# Power_Switching_Circuit_rev2.net
KiCad netlist of a schematic drawn in EAGLE
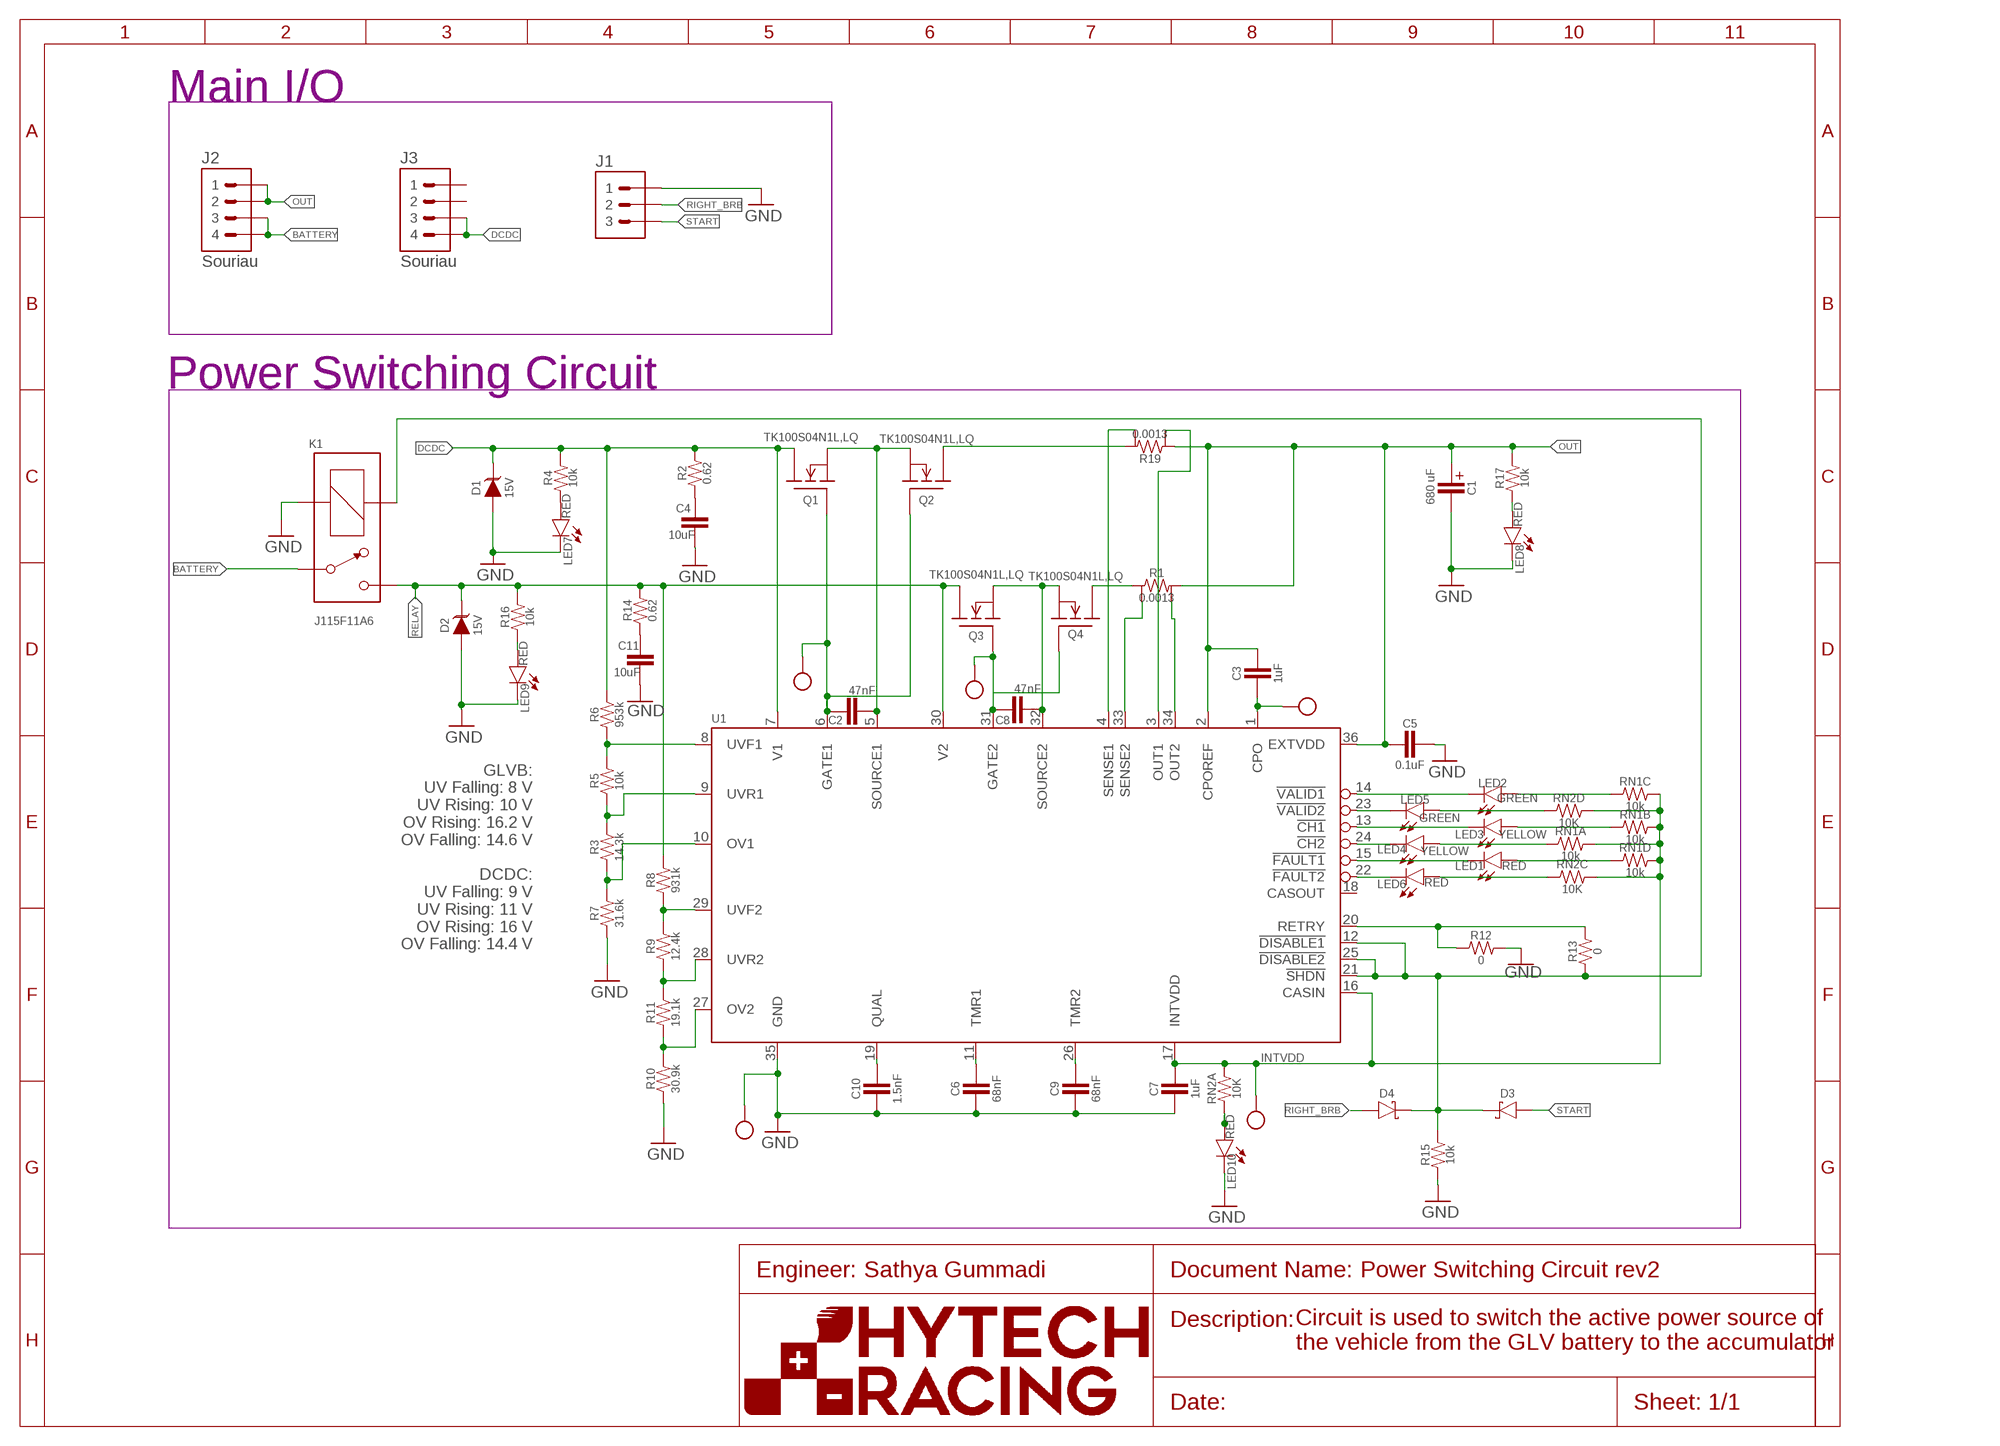
[diagram p0: schematic, sheet 1]

(export (version "E")
  (design (tool "Eeschema 10.0.6"))
  (components
    (comp (ref "C1")
      (value "CAPACITOR_POLARIZED")
      (footprint "eagle-import:EEE-FK1H681AM")
      (libsource (lib "eagle-import") (part "CAPACITOR_POLARIZED"))
    )
    (comp (ref "C2")
      (value "47nF")
      (footprint "eagle-import:0603-CAP@1")
      (libsource (lib "eagle-import") (part "CAP0603-CAP"))
    )
    (comp (ref "C3")
      (value "1uF")
      (footprint "eagle-import:0805")
      (libsource (lib "eagle-import") (part "CAP0805"))
    )
    (comp (ref "C4")
      (value "10uF")
      (footprint "eagle-import:1206-CAP")
      (libsource (lib "eagle-import") (part "CAPACITOR_VALUE1206"))
    )
    (comp (ref "C5")
      (value "0.1uF")
      (footprint "eagle-import:0603-CAP@1")
      (libsource (lib "eagle-import") (part "CAP0603-CAP"))
    )
    (comp (ref "C6")
      (value "68nF")
      (footprint "eagle-import:0603-CAP@1")
      (libsource (lib "eagle-import") (part "CAP0603-CAP"))
    )
    (comp (ref "C7")
      (value "1uF")
      (footprint "eagle-import:0805")
      (libsource (lib "eagle-import") (part "CAP0805"))
    )
    (comp (ref "C8")
      (value "47nF")
      (footprint "eagle-import:0603-CAP@1")
      (libsource (lib "eagle-import") (part "CAP0603-CAP"))
    )
    (comp (ref "C9")
      (value "68nF")
      (footprint "eagle-import:0603-CAP@1")
      (libsource (lib "eagle-import") (part "CAP0603-CAP"))
    )
    (comp (ref "C10")
      (value "1.5nF")
      (footprint "eagle-import:0603-CAP@1")
      (libsource (lib "eagle-import") (part "CAP0603-CAP"))
    )
    (comp (ref "C11")
      (value "10uF")
      (footprint "eagle-import:1206-CAP")
      (libsource (lib "eagle-import") (part "CAPACITOR_VALUE1206"))
    )
    (comp (ref "D1")
      (value "TVS_15V")
      (footprint "eagle-import:SOT-23")
      (fields
        (field (name "MANUFACTURER") "Vishay General Semiconductor - Diodes Division")
        (field (name "MPN") "GSOT15-E3-08")
        (field (name "VOLTAGE") "15V")
      )
      (libsource (lib "eagle-import") (part "TVS_15V"))
    )
    (comp (ref "D2")
      (value "TVS_15V")
      (footprint "eagle-import:SOT-23")
      (fields
        (field (name "MANUFACTURER") "Vishay General Semiconductor - Diodes Division")
        (field (name "MPN") "GSOT15-E3-08")
        (field (name "VOLTAGE") "15V")
      )
      (libsource (lib "eagle-import") (part "TVS_15V"))
    )
    (comp (ref "D3")
      (value "SCHOTTKY")
      (footprint "eagle-import:CLP1608-2L")
      (fields
        (field (name "MANUFACTURER") "Vishay General Semiconductor - Diodes Division")
        (field (name "MPN") "VSKY20401608-G4-08")
      )
      (libsource (lib "eagle-import") (part "SCHOTTKY"))
    )
    (comp (ref "D4")
      (value "SCHOTTKY")
      (footprint "eagle-import:CLP1608-2L")
      (fields
        (field (name "MANUFACTURER") "Vishay General Semiconductor - Diodes Division")
        (field (name "MPN") "VSKY20401608-G4-08")
      )
      (libsource (lib "eagle-import") (part "SCHOTTKY"))
    )
    (comp (ref "J1")
      (value "CONNECTOR-3_")
      (footprint "eagle-import:SOURIAU_04-35")
      (libsource (lib "eagle-import") (part "CONNECTOR-3_?"))
    )
    (comp (ref "J2")
      (value "CONNECTOR-4_SOURIAU_")
      (footprint "eagle-import:SOURIAU_12-04")
      (fields
        (field (name "MODEL") "Souriau")
        (field (name "MANUFACTURER") "Souriau")
        (field (name "MPN") "8STA21204PN ")
      )
      (libsource (lib "eagle-import") (part "CONNECTOR-4_?_SOURIAU"))
    )
    (comp (ref "J3")
      (value "CONNECTOR-4_SOURIAU_")
      (footprint "eagle-import:SOURIAU_12-04")
      (fields
        (field (name "MODEL") "Souriau")
        (field (name "MANUFACTURER") "Souriau")
        (field (name "MPN") "8STA21204PN ")
      )
      (libsource (lib "eagle-import") (part "CONNECTOR-4_?_SOURIAU"))
    )
    (comp (ref "K1")
      (value "J115F11A6")
      (footprint "eagle-import:J115F11A_6_")
      (libsource (lib "eagle-import") (part "J115F11A6"))
    )
    (comp (ref "LED1")
      (value "RED")
      (footprint "eagle-import:LED-603")
      (libsource (lib "eagle-import") (part "LED-0603"))
    )
    (comp (ref "LED2")
      (value "GREEN")
      (footprint "eagle-import:LED-603")
      (libsource (lib "eagle-import") (part "LED-0603"))
    )
    (comp (ref "LED3")
      (value "YELLOW")
      (footprint "eagle-import:LED-603")
      (libsource (lib "eagle-import") (part "LED-0603"))
    )
    (comp (ref "LED4")
      (value "YELLOW")
      (footprint "eagle-import:LED-603")
      (libsource (lib "eagle-import") (part "LED-0603"))
    )
    (comp (ref "LED5")
      (value "GREEN")
      (footprint "eagle-import:LED-603")
      (libsource (lib "eagle-import") (part "LED-0603"))
    )
    (comp (ref "LED6")
      (value "RED")
      (footprint "eagle-import:LED-603")
      (libsource (lib "eagle-import") (part "LED-0603"))
    )
    (comp (ref "LED7")
      (value "RED")
      (footprint "eagle-import:LED-603")
      (libsource (lib "eagle-import") (part "LED-0603"))
    )
    (comp (ref "LED8")
      (value "RED")
      (footprint "eagle-import:LED-603")
      (libsource (lib "eagle-import") (part "LED-0603"))
    )
    (comp (ref "LED9")
      (value "RED")
      (footprint "eagle-import:LED-603")
      (libsource (lib "eagle-import") (part "LED-0603"))
    )
    (comp (ref "LED10")
      (value "RED")
      (footprint "eagle-import:LED-603")
      (libsource (lib "eagle-import") (part "LED-0603"))
    )
    (comp (ref "Q1")
      (value "TK100S04N1L")
      (footprint "eagle-import:TO-252-3")
      (fields (field (name "MPN") "TK100S04N1L,LQ"))
      (libsource (lib "eagle-import") (part "TK100S04N1L"))
    )
    (comp (ref "Q2")
      (value "TK100S04N1L")
      (footprint "eagle-import:TO-252-3")
      (fields (field (name "MPN") "TK100S04N1L,LQ"))
      (libsource (lib "eagle-import") (part "TK100S04N1L"))
    )
    (comp (ref "Q3")
      (value "TK100S04N1L")
      (footprint "eagle-import:TO-252-3")
      (fields (field (name "MPN") "TK100S04N1L,LQ"))
      (libsource (lib "eagle-import") (part "TK100S04N1L"))
    )
    (comp (ref "Q4")
      (value "TK100S04N1L")
      (footprint "eagle-import:TO-252-3")
      (fields (field (name "MPN") "TK100S04N1L,LQ"))
      (libsource (lib "eagle-import") (part "TK100S04N1L"))
    )
    (comp (ref "R1")
      (value "RESISTOR_SENSE")
      (footprint "eagle-import:WSL2726")
      (fields (field (name "RESISTANCE") "0.0013") (field (name "MPN") "WSL2726"))
      (libsource (lib "eagle-import") (part "RESISTOR_SENSE"))
    )
    (comp (ref "R2")
      (value "0.62")
      (footprint "eagle-import:0805")
      (libsource (lib "eagle-import") (part "RESISTOR0805"))
    )
    (comp (ref "R3")
      (value "14.3k")
      (footprint "eagle-import:0603-RES")
      (libsource (lib "eagle-import") (part "RESISTOR0603"))
    )
    (comp (ref "R4")
      (value "10k")
      (footprint "eagle-import:0603-RES")
      (libsource (lib "eagle-import") (part "RESISTOR0603"))
    )
    (comp (ref "R5")
      (value "10k")
      (footprint "eagle-import:0603-RES")
      (libsource (lib "eagle-import") (part "RESISTOR0603"))
    )
    (comp (ref "R6")
      (value "953k")
      (footprint "eagle-import:0603-RES")
      (libsource (lib "eagle-import") (part "RESISTOR0603"))
    )
    (comp (ref "R7")
      (value "31.6k")
      (footprint "eagle-import:0603-RES")
      (libsource (lib "eagle-import") (part "RESISTOR0603"))
    )
    (comp (ref "R8")
      (value "931k")
      (footprint "eagle-import:0603-RES")
      (libsource (lib "eagle-import") (part "RESISTOR0603"))
    )
    (comp (ref "R9")
      (value "12.4k")
      (footprint "eagle-import:0603-RES")
      (libsource (lib "eagle-import") (part "RESISTOR0603"))
    )
    (comp (ref "R10")
      (value "30.9k")
      (footprint "eagle-import:0603-RES")
      (libsource (lib "eagle-import") (part "RESISTOR0603"))
    )
    (comp (ref "R11")
      (value "19.1k")
      (footprint "eagle-import:0603-RES")
      (libsource (lib "eagle-import") (part "RESISTOR0603"))
    )
    (comp (ref "R12")
      (value "0")
      (footprint "eagle-import:0603-RES")
      (libsource (lib "eagle-import") (part "RESISTOR0603"))
    )
    (comp (ref "R13")
      (value "0")
      (footprint "eagle-import:0603-RES")
      (libsource (lib "eagle-import") (part "RESISTOR0603"))
    )
    (comp (ref "R14")
      (value "0.62")
      (footprint "eagle-import:0805")
      (libsource (lib "eagle-import") (part "RESISTOR0805"))
    )
    (comp (ref "R15")
      (value "10k")
      (footprint "eagle-import:0603-RES")
      (libsource (lib "eagle-import") (part "RESISTOR0603"))
    )
    (comp (ref "R16")
      (value "10k")
      (footprint "eagle-import:0603-RES")
      (libsource (lib "eagle-import") (part "RESISTOR0603"))
    )
    (comp (ref "R17")
      (value "10k")
      (footprint "eagle-import:0603-RES")
      (libsource (lib "eagle-import") (part "RESISTOR0603"))
    )
    (comp (ref "R19")
      (value "RESISTOR_SENSE")
      (footprint "eagle-import:WSL2726")
      (fields (field (name "RESISTANCE") "0.0013") (field (name "MPN") "WSL2726"))
      (libsource (lib "eagle-import") (part "RESISTOR_SENSE"))
    )
    (comp (ref "RN1")
      (value "RESISTOR_NETWORK_4_10K")
      (footprint "eagle-import:YC_TC164")
      (fields (field (name "RESISTANCE") "10k"))
      (libsource (lib "eagle-import") (part "HyTechDevices - Copy_RESISTOR_NETWORK_4_10K"))
    )
    (comp (ref "RN2")
      (value "RESISTOR_NETWORK_4_10K")
      (footprint "eagle-import:1206-RES")
      (fields
        (field (name "MANUFACTURER") "Yageo")
        (field (name "MPN") "TC164-FR-0710KL")
        (field (name "POWER") "1/16W")
        (field (name "RESISTANCE") "10K")
      )
      (libsource (lib "eagle-import") (part "RESISTOR_NETWORK_4_10K"))
    )
    (comp (ref "U$7")
      (value "TEST_POINTMICRO_MINIATURE")
      (footprint "eagle-import:MICRO_MINIATURE")
      (libsource (lib "eagle-import") (part "TEST_POINTMICRO_MINIATURE"))
    )
    (comp (ref "U$8")
      (value "TEST_POINTMICRO_MINIATURE")
      (footprint "eagle-import:MICRO_MINIATURE")
      (libsource (lib "eagle-import") (part "TEST_POINTMICRO_MINIATURE"))
    )
    (comp (ref "U$9")
      (value "TEST_POINTMICRO_MINIATURE")
      (footprint "eagle-import:MICRO_MINIATURE")
      (libsource (lib "eagle-import") (part "TEST_POINTMICRO_MINIATURE"))
    )
    (comp (ref "U$10")
      (value "TEST_POINTMICRO_MINIATURE")
      (footprint "eagle-import:MICRO_MINIATURE")
      (libsource (lib "eagle-import") (part "TEST_POINTMICRO_MINIATURE"))
    )
    (comp (ref "U$11")
      (value "TEST_POINTMICRO_MINIATURE")
      (footprint "eagle-import:MICRO_MINIATURE")
      (libsource (lib "eagle-import") (part "TEST_POINTMICRO_MINIATURE"))
    )
    (comp (ref "U1")
      (value "LTC4421")
      (footprint "eagle-import:SSOP-36")
      (libsource (lib "eagle-import") (part "LTC4421"))
    )
  )
  (nets
    (net (code "1") (name "/INTVDD") (class "Default")
      (node (ref "C7") (pin "1") (pinfunction "1_1") (pintype "passive"))
      (node (ref "RN1") (pin "5") (pinfunction "2_5") (pintype "passive"))
      (node (ref "RN1") (pin "6") (pinfunction "2_6") (pintype "passive"))
      (node (ref "RN1") (pin "7") (pinfunction "2_7") (pintype "passive"))
      (node (ref "RN1") (pin "8") (pinfunction "2_8") (pintype "passive"))
      (node (ref "RN2") (pin "5") (pinfunction "2_5") (pintype "passive"))
      (node (ref "RN2") (pin "6") (pinfunction "2_6") (pintype "passive"))
      (node (ref "RN2") (pin "8") (pinfunction "2_8") (pintype "passive"))
      (node (ref "U$8") (pin "P$1") (pinfunction "P$1_P$1") (pintype "bidirectional"))
      (node (ref "U1") (pin "16") (pinfunction "CASIN_16") (pintype "input"))
      (node (ref "U1") (pin "17") (pinfunction "INTVDD_17") (pintype "power_in"))
    )
    (net (code "2") (name "BATTERY") (class "Default")
      (node (ref "J2") (pin "3") (pinfunction "3_3") (pintype "passive"))
      (node (ref "J2") (pin "4") (pinfunction "4_4") (pintype "passive"))
      (node (ref "K1") (pin "CONTACT1") (pinfunction "P_CONTACT1") (pintype "bidirectional"))
    )
    (net (code "3") (name "DCDC") (class "Default")
      (node (ref "D1") (pin "3") (pinfunction "C_3") (pintype "passive"))
      (node (ref "J3") (pin "3") (pinfunction "3_3") (pintype "passive"))
      (node (ref "J3") (pin "4") (pinfunction "4_4") (pintype "passive"))
      (node (ref "Q1") (pin "2") (pinfunction "D_2") (pintype "passive"))
      (node (ref "R2") (pin "2") (pinfunction "2_2") (pintype "passive"))
      (node (ref "R4") (pin "2") (pinfunction "2_2") (pintype "passive"))
      (node (ref "R6") (pin "2") (pinfunction "2_2") (pintype "passive"))
      (node (ref "U1") (pin "7") (pinfunction "V1_7") (pintype "input"))
    )
    (net (code "4") (name "GND") (class "Default")
      (node (ref "C1") (pin "P$2") (pinfunction "MINUS_P$2") (pintype "passive"))
      (node (ref "C10") (pin "2") (pinfunction "2_2") (pintype "passive"))
      (node (ref "C11") (pin "2") (pinfunction "2_2") (pintype "passive"))
      (node (ref "C4") (pin "2") (pinfunction "2_2") (pintype "passive"))
      (node (ref "C5") (pin "1") (pinfunction "1_1") (pintype "passive"))
      (node (ref "C6") (pin "2") (pinfunction "2_2") (pintype "passive"))
      (node (ref "C7") (pin "2") (pinfunction "2_2") (pintype "passive"))
      (node (ref "C9") (pin "2") (pinfunction "2_2") (pintype "passive"))
      (node (ref "D1") (pin "1") (pinfunction "A_1") (pintype "passive"))
      (node (ref "D2") (pin "1") (pinfunction "A_1") (pintype "passive"))
      (node (ref "J1") (pin "A") (pinfunction "1_A") (pintype "passive"))
      (node (ref "K1") (pin "COIL2") (pinfunction "COIL-_COIL2") (pintype "bidirectional"))
      (node (ref "LED10") (pin "C") (pinfunction "C_C") (pintype "passive"))
      (node (ref "LED7") (pin "C") (pinfunction "C_C") (pintype "passive"))
      (node (ref "LED8") (pin "C") (pinfunction "C_C") (pintype "passive"))
      (node (ref "LED9") (pin "C") (pinfunction "C_C") (pintype "passive"))
      (node (ref "R10") (pin "1") (pinfunction "1_1") (pintype "passive"))
      (node (ref "R12") (pin "2") (pinfunction "2_2") (pintype "passive"))
      (node (ref "R15") (pin "1") (pinfunction "1_1") (pintype "passive"))
      (node (ref "R7") (pin "1") (pinfunction "1_1") (pintype "passive"))
      (node (ref "U$11") (pin "P$1") (pinfunction "P$1_P$1") (pintype "bidirectional"))
      (node (ref "U1") (pin "35") (pinfunction "GND_35") (pintype "power_in"))
    )
    (net (code "5") (name "Net-(C4-Pad1)") (class "Default")
      (node (ref "C4") (pin "1") (pinfunction "1_1") (pintype "passive"))
      (node (ref "R2") (pin "1") (pinfunction "1_1") (pintype "passive"))
    )
    (net (code "6") (name "Net-(C11-Pad1)") (class "Default")
      (node (ref "C11") (pin "1") (pinfunction "1_1") (pintype "passive"))
      (node (ref "R14") (pin "1") (pinfunction "1_1") (pintype "passive"))
    )
    (net (code "7") (name "Net-(D3-C)") (class "Default")
      (node (ref "D3") (pin "2") (pinfunction "C_2") (pintype "passive"))
      (node (ref "D4") (pin "2") (pinfunction "C_2") (pintype "passive"))
      (node (ref "K1") (pin "COIL1") (pinfunction "COIL+_COIL1") (pintype "bidirectional"))
      (node (ref "R13") (pin "1") (pinfunction "1_1") (pintype "passive"))
      (node (ref "R15") (pin "2") (pinfunction "2_2") (pintype "passive"))
      (node (ref "U1") (pin "12") (pinfunction "~{DISABLE1}_12") (pintype "input"))
      (node (ref "U1") (pin "21") (pinfunction "~{SHDN}_21") (pintype "input"))
      (node (ref "U1") (pin "25") (pinfunction "~{DISABLE2}_25") (pintype "input"))
    )
    (net (code "8") (name "Net-(LED4-PadA)") (class "Default")
      (node (ref "LED4") (pin "A") (pinfunction "A_A") (pintype "passive"))
      (node (ref "RN1") (pin "1") (pinfunction "1_1") (pintype "passive"))
    )
    (net (code "9") (name "Net-(LED7-PadA)") (class "Default")
      (node (ref "LED7") (pin "A") (pinfunction "A_A") (pintype "passive"))
      (node (ref "R4") (pin "1") (pinfunction "1_1") (pintype "passive"))
    )
    (net (code "10") (name "Net-(LED8-PadA)") (class "Default")
      (node (ref "LED8") (pin "A") (pinfunction "A_A") (pintype "passive"))
      (node (ref "R17") (pin "1") (pinfunction "1_1") (pintype "passive"))
    )
    (net (code "11") (name "Net-(LED9-PadA)") (class "Default")
      (node (ref "LED9") (pin "A") (pinfunction "A_A") (pintype "passive"))
      (node (ref "R16") (pin "1") (pinfunction "1_1") (pintype "passive"))
    )
    (net (code "12") (name "Net-(LED10-PadA)") (class "Default")
      (node (ref "LED10") (pin "A") (pinfunction "A_A") (pintype "passive"))
      (node (ref "RN2") (pin "1") (pinfunction "1_1") (pintype "passive"))
    )
    (net (code "13") (name "Net-(Q1-G)") (class "Default")
      (node (ref "C2") (pin "2") (pinfunction "2_2") (pintype "passive"))
      (node (ref "Q1") (pin "1") (pinfunction "G_1") (pintype "passive"))
      (node (ref "Q2") (pin "1") (pinfunction "G_1") (pintype "passive"))
      (node (ref "U$10") (pin "P$1") (pinfunction "P$1_P$1") (pintype "bidirectional"))
      (node (ref "U1") (pin "6") (pinfunction "GATE1_6") (pintype "input"))
    )
    (net (code "14") (name "Net-(Q1-S)") (class "Default")
      (node (ref "C2") (pin "1") (pinfunction "1_1") (pintype "passive"))
      (node (ref "Q1") (pin "3") (pinfunction "S_3") (pintype "passive"))
      (node (ref "Q2") (pin "3") (pinfunction "S_3") (pintype "passive"))
      (node (ref "U1") (pin "5") (pinfunction "SOURCE1_5") (pintype "input"))
    )
    (net (code "15") (name "Net-(Q2-D)") (class "Default")
      (node (ref "Q2") (pin "2") (pinfunction "D_2") (pintype "passive"))
      (node (ref "R19") (pin "2") (pinfunction "2_2") (pintype "passive"))
    )
    (net (code "16") (name "Net-(Q3-G)") (class "Default")
      (node (ref "C8") (pin "2") (pinfunction "2_2") (pintype "passive"))
      (node (ref "Q3") (pin "1") (pinfunction "G_1") (pintype "passive"))
      (node (ref "Q4") (pin "1") (pinfunction "G_1") (pintype "passive"))
      (node (ref "U$7") (pin "P$1") (pinfunction "P$1_P$1") (pintype "bidirectional"))
      (node (ref "U1") (pin "31") (pinfunction "GATE2_31") (pintype "input"))
    )
    (net (code "17") (name "Net-(Q3-S)") (class "Default")
      (node (ref "C8") (pin "1") (pinfunction "1_1") (pintype "passive"))
      (node (ref "Q3") (pin "3") (pinfunction "S_3") (pintype "passive"))
      (node (ref "Q4") (pin "3") (pinfunction "S_3") (pintype "passive"))
      (node (ref "U1") (pin "32") (pinfunction "SOURCE2_32") (pintype "input"))
    )
    (net (code "18") (name "Net-(Q4-D)") (class "Default")
      (node (ref "Q4") (pin "2") (pinfunction "D_2") (pintype "passive"))
      (node (ref "R1") (pin "1") (pinfunction "1_1") (pintype "passive"))
    )
    (net (code "19") (name "Net-(RN1B-1)") (class "Default")
      (node (ref "LED3") (pin "A") (pinfunction "A_A") (pintype "passive"))
      (node (ref "RN1") (pin "2") (pinfunction "1_2") (pintype "passive"))
    )
    (net (code "20") (name "Net-(RN1C-1)") (class "Default")
      (node (ref "LED2") (pin "A") (pinfunction "A_A") (pintype "passive"))
      (node (ref "RN1") (pin "3") (pinfunction "1_3") (pintype "passive"))
    )
    (net (code "21") (name "Net-(RN1D-1)") (class "Default")
      (node (ref "LED1") (pin "A") (pinfunction "A_A") (pintype "passive"))
      (node (ref "RN1") (pin "4") (pinfunction "1_4") (pintype "passive"))
    )
    (net (code "22") (name "Net-(RN2C-1)") (class "Default")
      (node (ref "LED6") (pin "A") (pinfunction "A_A") (pintype "passive"))
      (node (ref "RN2") (pin "3") (pinfunction "1_3") (pintype "passive"))
    )
    (net (code "23") (name "Net-(RN2D-1)") (class "Default")
      (node (ref "LED5") (pin "A") (pinfunction "A_A") (pintype "passive"))
      (node (ref "RN2") (pin "4") (pinfunction "1_4") (pintype "passive"))
    )
    (net (code "24") (name "Net-(U1-CPO)") (class "Default")
      (node (ref "C3") (pin "2") (pinfunction "2_2") (pintype "passive"))
      (node (ref "U$9") (pin "P$1") (pinfunction "P$1_P$1") (pintype "bidirectional"))
      (node (ref "U1") (pin "1") (pinfunction "CPO_1") (pintype "input"))
    )
    (net (code "25") (name "Net-(U1-OUT1)") (class "Default")
      (node (ref "R19") (pin "3") (pinfunction "3_3") (pintype "passive"))
      (node (ref "U1") (pin "3") (pinfunction "OUT1_3") (pintype "input"))
    )
    (net (code "26") (name "Net-(U1-OUT2)") (class "Default")
      (node (ref "R1") (pin "4") (pinfunction "4_4") (pintype "passive"))
      (node (ref "U1") (pin "34") (pinfunction "OUT2_34") (pintype "input"))
    )
    (net (code "27") (name "Net-(U1-OV1)") (class "Default")
      (node (ref "R3") (pin "1") (pinfunction "1_1") (pintype "passive"))
      (node (ref "R7") (pin "2") (pinfunction "2_2") (pintype "passive"))
      (node (ref "U1") (pin "10") (pinfunction "OV1_10") (pintype "input"))
    )
    (net (code "28") (name "Net-(U1-OV2)") (class "Default")
      (node (ref "R10") (pin "2") (pinfunction "2_2") (pintype "passive"))
      (node (ref "R11") (pin "1") (pinfunction "1_1") (pintype "passive"))
      (node (ref "U1") (pin "27") (pinfunction "OV2_27") (pintype "input"))
    )
    (net (code "29") (name "Net-(U1-QUAL)") (class "Default")
      (node (ref "C10") (pin "1") (pinfunction "1_1") (pintype "passive"))
      (node (ref "U1") (pin "19") (pinfunction "QUAL_19") (pintype "bidirectional"))
    )
    (net (code "30") (name "Net-(U1-RETRY)") (class "Default")
      (node (ref "R12") (pin "1") (pinfunction "1_1") (pintype "passive"))
      (node (ref "R13") (pin "2") (pinfunction "2_2") (pintype "passive"))
      (node (ref "U1") (pin "20") (pinfunction "RETRY_20") (pintype "input"))
    )
    (net (code "31") (name "Net-(U1-SENSE1)") (class "Default")
      (node (ref "R19") (pin "4") (pinfunction "4_4") (pintype "passive"))
      (node (ref "U1") (pin "4") (pinfunction "SENSE1_4") (pintype "input"))
    )
    (net (code "32") (name "Net-(U1-SENSE2)") (class "Default")
      (node (ref "R1") (pin "3") (pinfunction "3_3") (pintype "passive"))
      (node (ref "U1") (pin "33") (pinfunction "SENSE2_33") (pintype "input"))
    )
    (net (code "33") (name "Net-(U1-TMR1)") (class "Default")
      (node (ref "C6") (pin "1") (pinfunction "1_1") (pintype "passive"))
      (node (ref "U1") (pin "11") (pinfunction "TMR1_11") (pintype "bidirectional"))
    )
    (net (code "34") (name "Net-(U1-TMR2)") (class "Default")
      (node (ref "C9") (pin "1") (pinfunction "1_1") (pintype "passive"))
      (node (ref "U1") (pin "26") (pinfunction "TMR2_26") (pintype "bidirectional"))
    )
    (net (code "35") (name "Net-(U1-UVF1)") (class "Default")
      (node (ref "R5") (pin "2") (pinfunction "2_2") (pintype "passive"))
      (node (ref "R6") (pin "1") (pinfunction "1_1") (pintype "passive"))
      (node (ref "U1") (pin "8") (pinfunction "UVF1_8") (pintype "input"))
    )
    (net (code "36") (name "Net-(U1-UVF2)") (class "Default")
      (node (ref "R8") (pin "1") (pinfunction "1_1") (pintype "passive"))
      (node (ref "R9") (pin "2") (pinfunction "2_2") (pintype "passive"))
      (node (ref "U1") (pin "29") (pinfunction "UVF2_29") (pintype "input"))
    )
    (net (code "37") (name "Net-(U1-UVR1)") (class "Default")
      (node (ref "R3") (pin "2") (pinfunction "2_2") (pintype "passive"))
      (node (ref "R5") (pin "1") (pinfunction "1_1") (pintype "passive"))
      (node (ref "U1") (pin "9") (pinfunction "UVR1_9") (pintype "input"))
    )
    (net (code "38") (name "Net-(U1-UVR2)") (class "Default")
      (node (ref "R11") (pin "2") (pinfunction "2_2") (pintype "passive"))
      (node (ref "R9") (pin "1") (pinfunction "1_1") (pintype "passive"))
      (node (ref "U1") (pin "28") (pinfunction "UVR2_28") (pintype "input"))
    )
    (net (code "39") (name "Net-(U1-~{CH1})") (class "Default")
      (node (ref "LED3") (pin "C") (pinfunction "C_C") (pintype "passive"))
      (node (ref "U1") (pin "13") (pinfunction "~{CH1}_13") (pintype "open_collector"))
    )
    (net (code "40") (name "Net-(U1-~{CH2})") (class "Default")
      (node (ref "LED4") (pin "C") (pinfunction "C_C") (pintype "passive"))
      (node (ref "U1") (pin "24") (pinfunction "~{CH2}_24") (pintype "open_collector"))
    )
    (net (code "41") (name "Net-(U1-~{FAULT1})") (class "Default")
      (node (ref "LED1") (pin "C") (pinfunction "C_C") (pintype "passive"))
      (node (ref "U1") (pin "15") (pinfunction "~{FAULT1}_15") (pintype "open_collector"))
    )
    (net (code "42") (name "Net-(U1-~{FAULT2})") (class "Default")
      (node (ref "LED6") (pin "C") (pinfunction "C_C") (pintype "passive"))
      (node (ref "U1") (pin "22") (pinfunction "~{FAULT2}_22") (pintype "open_collector"))
    )
    (net (code "43") (name "Net-(U1-~{VALID1})") (class "Default")
      (node (ref "LED2") (pin "C") (pinfunction "C_C") (pintype "passive"))
      (node (ref "U1") (pin "14") (pinfunction "~{VALID1}_14") (pintype "open_collector"))
    )
    (net (code "44") (name "Net-(U1-~{VALID2})") (class "Default")
      (node (ref "LED5") (pin "C") (pinfunction "C_C") (pintype "passive"))
      (node (ref "U1") (pin "23") (pinfunction "~{VALID2}_23") (pintype "open_collector"))
    )
    (net (code "45") (name "OUT") (class "Default")
      (node (ref "C1") (pin "P$1") (pinfunction "PLUS_P$1") (pintype "passive"))
      (node (ref "C3") (pin "1") (pinfunction "1_1") (pintype "passive"))
      (node (ref "C5") (pin "2") (pinfunction "2_2") (pintype "passive"))
      (node (ref "J2") (pin "1") (pinfunction "1_1") (pintype "passive"))
      (node (ref "J2") (pin "2") (pinfunction "2_2") (pintype "passive"))
      (node (ref "R1") (pin "2") (pinfunction "2_2") (pintype "passive"))
      (node (ref "R17") (pin "2") (pinfunction "2_2") (pintype "passive"))
      (node (ref "R19") (pin "1") (pinfunction "1_1") (pintype "passive"))
      (node (ref "U1") (pin "2") (pinfunction "CPOREF_2") (pintype "input"))
      (node (ref "U1") (pin "36") (pinfunction "EXTVDD_36") (pintype "power_in"))
    )
    (net (code "46") (name "RELAY") (class "Default")
      (node (ref "D2") (pin "3") (pinfunction "C_3") (pintype "passive"))
      (node (ref "K1") (pin "CONTACT2") (pinfunction "S_CONTACT2") (pintype "bidirectional"))
      (node (ref "Q3") (pin "2") (pinfunction "D_2") (pintype "passive"))
      (node (ref "R14") (pin "2") (pinfunction "2_2") (pintype "passive"))
      (node (ref "R16") (pin "2") (pinfunction "2_2") (pintype "passive"))
      (node (ref "R8") (pin "2") (pinfunction "2_2") (pintype "passive"))
      (node (ref "U1") (pin "30") (pinfunction "V2_30") (pintype "input"))
    )
    (net (code "47") (name "RIGHT_BRB") (class "Default")
      (node (ref "D4") (pin "1") (pinfunction "A_1") (pintype "passive"))
      (node (ref "J1") (pin "B") (pinfunction "2_B") (pintype "passive"))
    )
    (net (code "48") (name "START") (class "Default")
      (node (ref "D3") (pin "1") (pinfunction "A_1") (pintype "passive"))
      (node (ref "J1") (pin "C") (pinfunction "3_C") (pintype "passive"))
    )
    (net (code "49") (name "unconnected-(J3-Pad1)") (class "Default")
      (node (ref "J3") (pin "1") (pinfunction "1_1") (pintype "passive"))
    )
    (net (code "50") (name "unconnected-(J3-Pad2)") (class "Default")
      (node (ref "J3") (pin "2") (pinfunction "2_2") (pintype "passive"))
    )
    (net (code "51") (name "unconnected-(U1-CASOUT-Pad18)") (class "Default")
      (node (ref "U1") (pin "18") (pinfunction "CASOUT_18") (pintype "output"))
    )
  )
)
